# BluePillF4.net
KiCad netlist of a schematic drawn in EAGLE
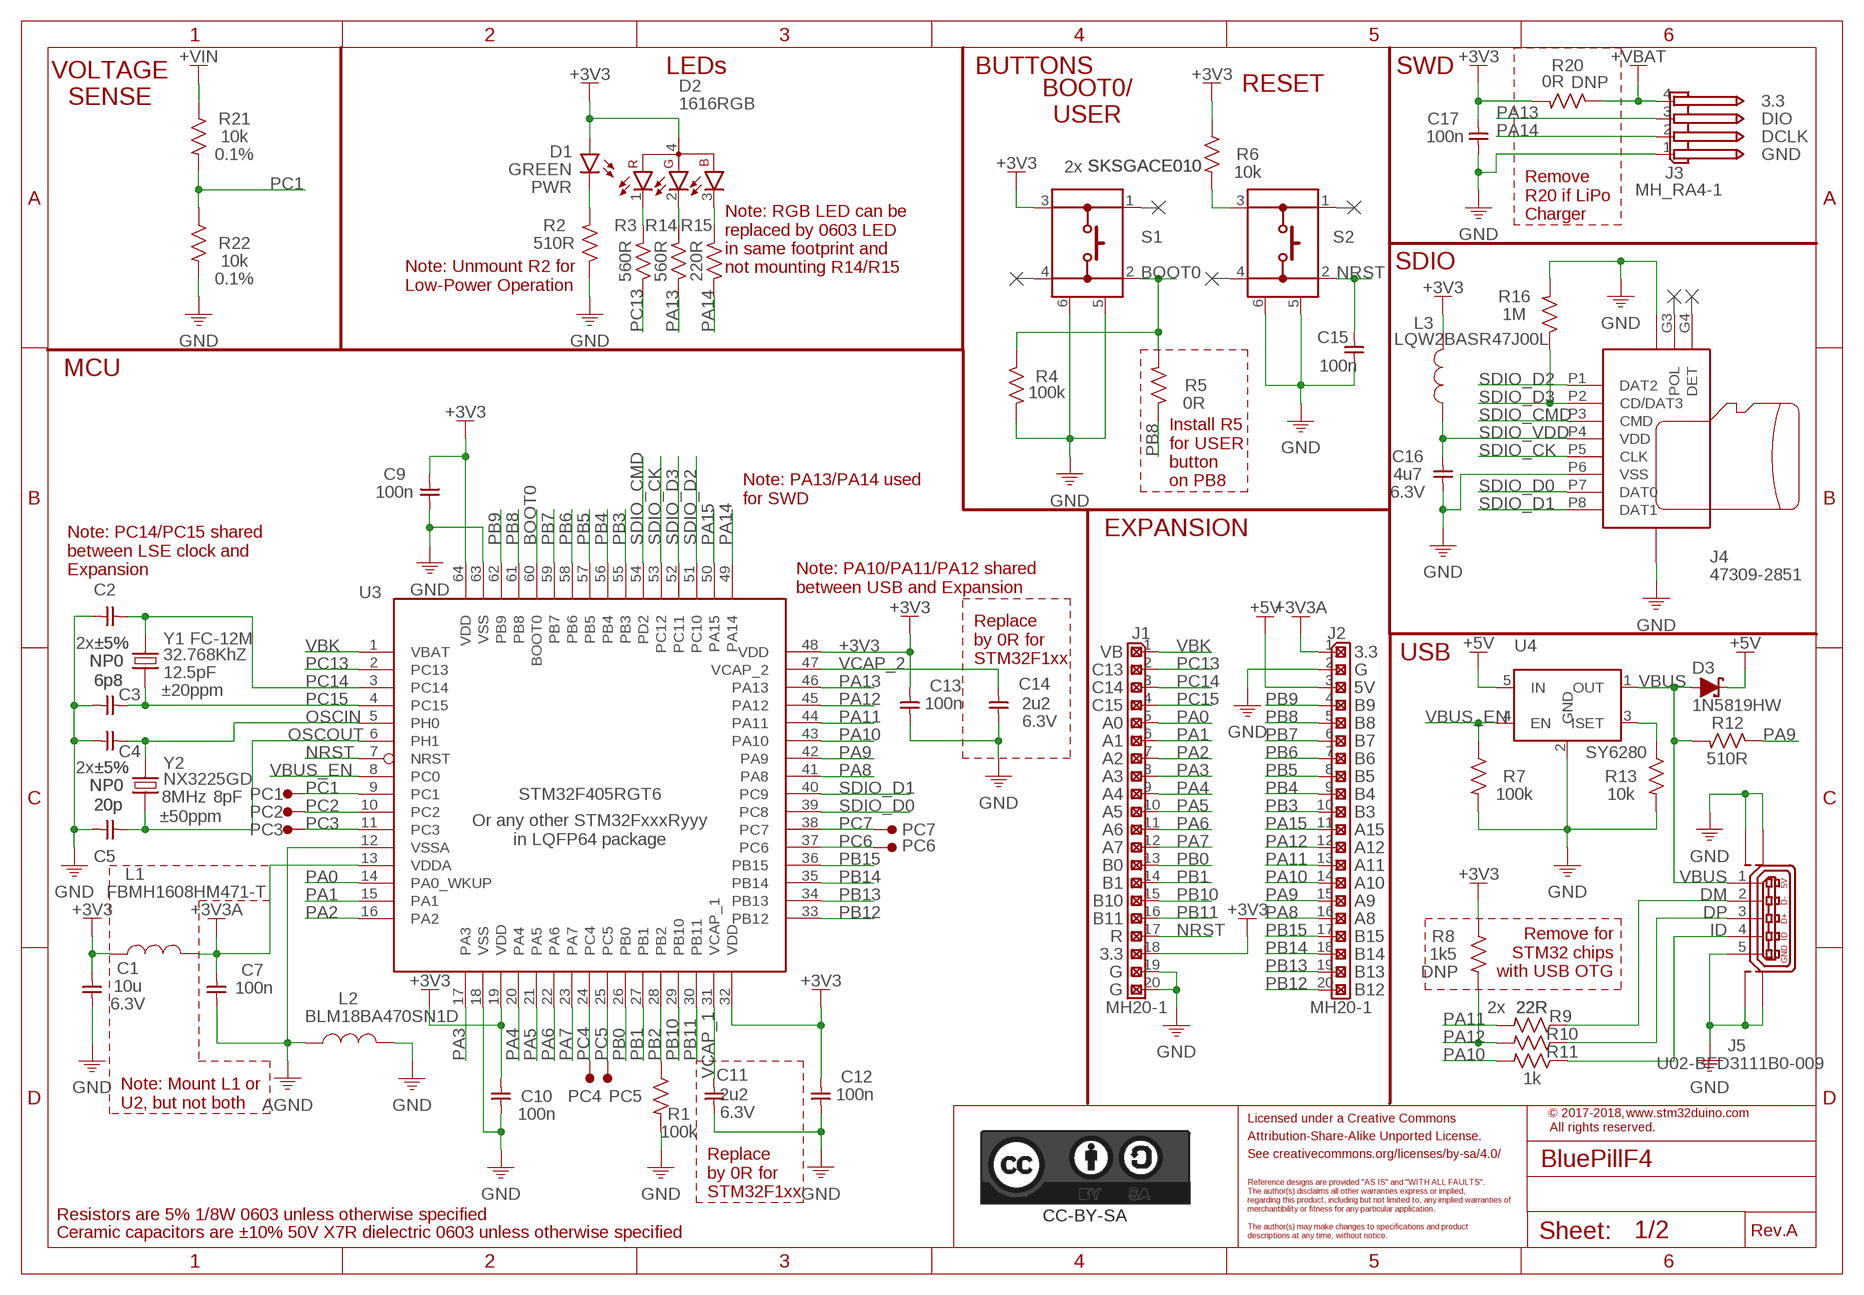
[diagram p0: schematic, sheet 1]
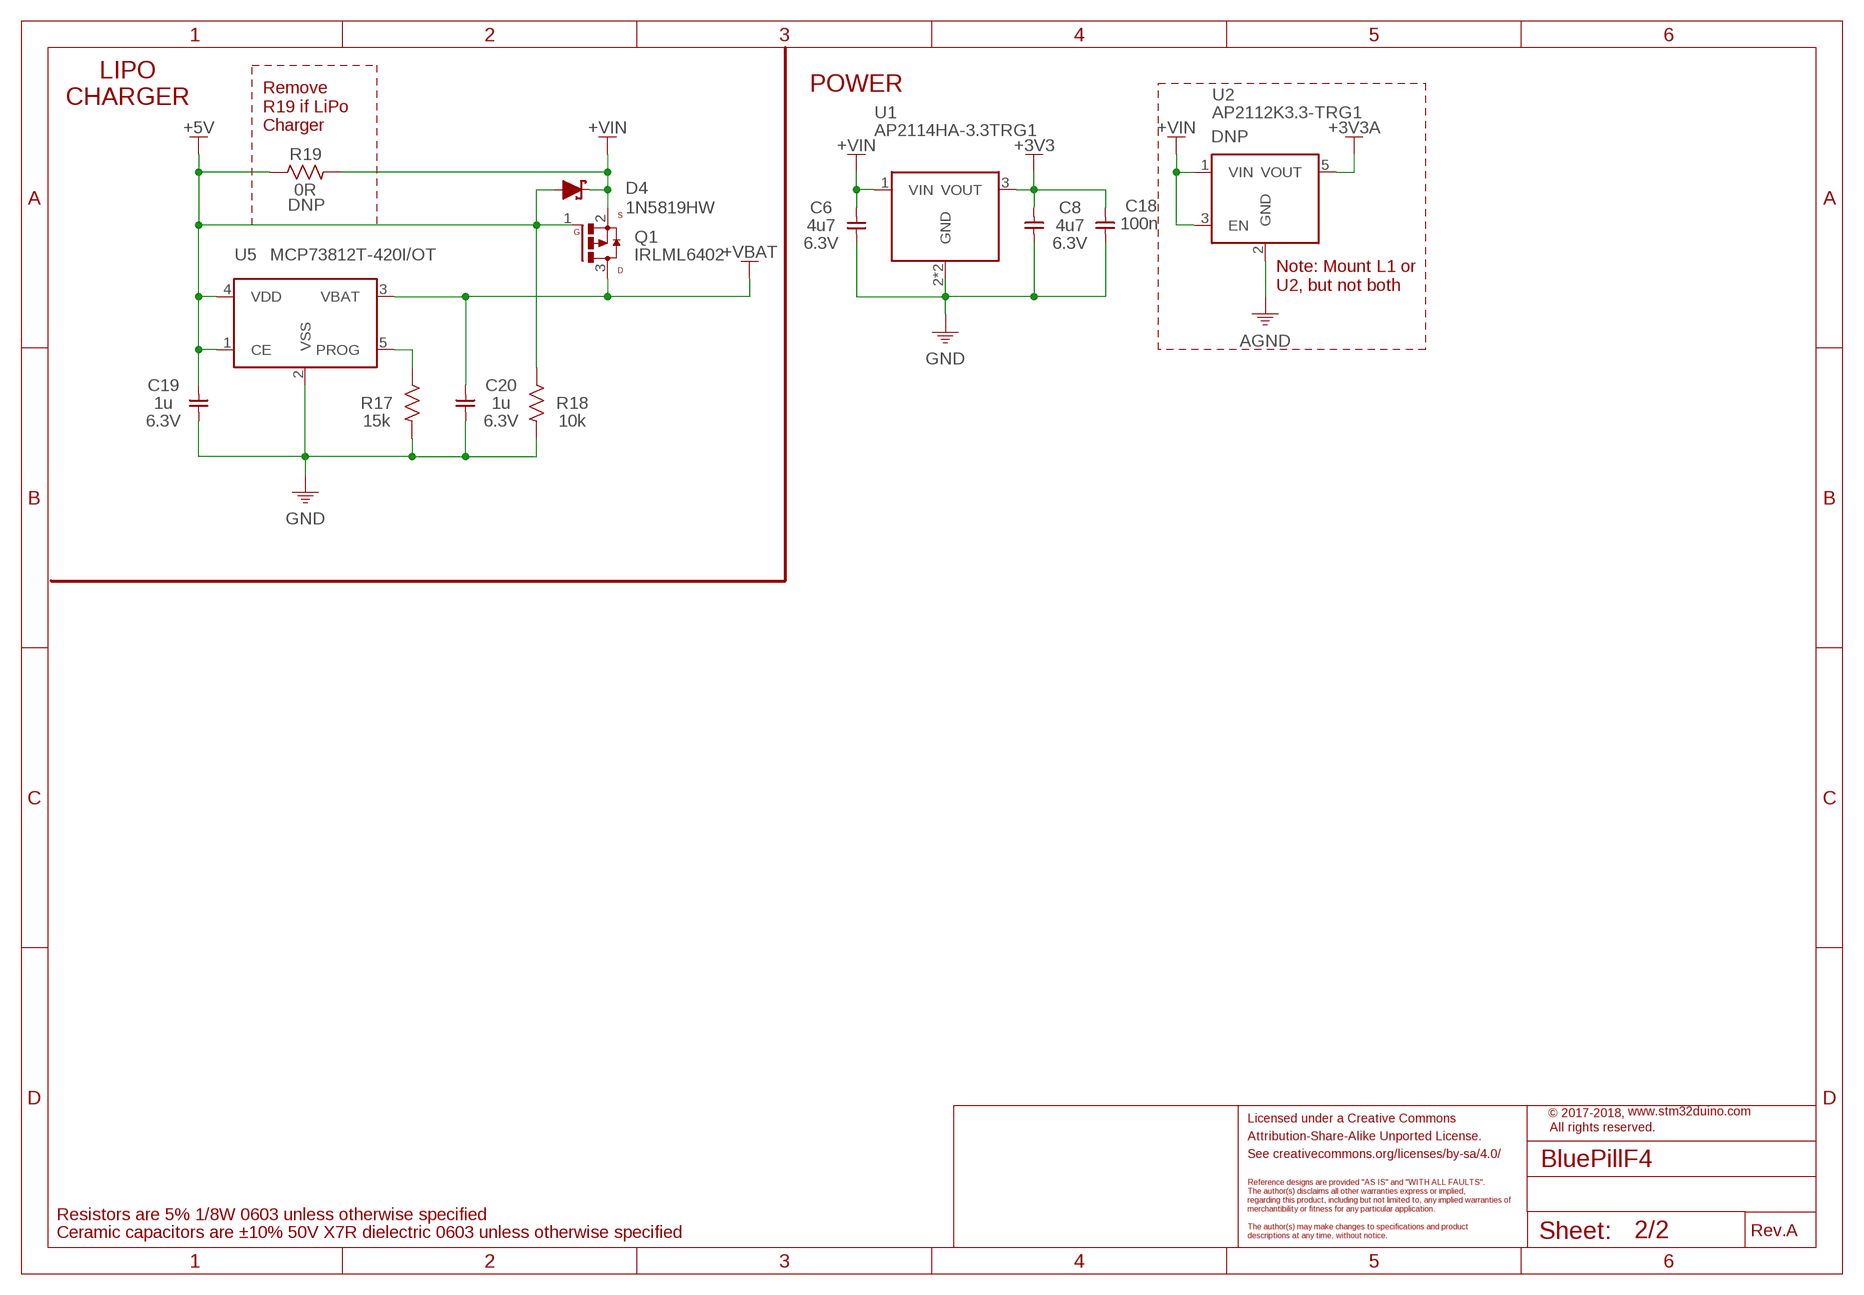
[diagram p1: schematic, sheet 2]

(export (version "E")
  (design (tool "Eeschema 10.0.6"))
  (components
    (comp (ref "C1")
      (value "10u")
      (footprint "eagle-import:C0603")
      (fields (field (name "PARTNO") "C0603_10u_X7R_10%_CER_6V3") (field (name "VOLT") "6.3V"))
      (libsource (lib "eagle-import") (part "CAP_0603"))
    )
    (comp (ref "C2")
      (value "6p8")
      (footprint "eagle-import:C0603")
      (fields
        (field (name "PARTNO") "C0603_6p8_NP0_5%_CER_50V")
        (field (name "TC") "NP0")
        (field (name "TOL") "±5%")
      )
      (libsource (lib "eagle-import") (part "CAP_0603"))
    )
    (comp (ref "C3")
      (value "6p8")
      (footprint "eagle-import:C0603")
      (fields
        (field (name "PARTNO") "C0603_6p8_NP0_5%_CER_50V")
        (field (name "TC") "NP0")
        (field (name "TOL") "±5%")
      )
      (libsource (lib "eagle-import") (part "CAP_0603"))
    )
    (comp (ref "C4")
      (value "20p")
      (footprint "eagle-import:C0603")
      (fields
        (field (name "PARTNO") "C0603_20p_NP0_5%_CER_50V")
        (field (name "TC") "NP0")
        (field (name "TOL") "±5%")
      )
      (libsource (lib "eagle-import") (part "CAP_0603"))
    )
    (comp (ref "C5")
      (value "20p")
      (footprint "eagle-import:C0603")
      (fields
        (field (name "PARTNO") "C0603_20p_NP0_5%_CER_50V")
        (field (name "TC") "NP0")
        (field (name "TOL") "±5%")
      )
      (libsource (lib "eagle-import") (part "CAP_0603"))
    )
    (comp (ref "C7")
      (value "100n")
      (footprint "eagle-import:C0603")
      (fields (field (name "PARTNO") "C0603_100n_X7R_10%_CER_50V"))
      (libsource (lib "eagle-import") (part "CAP_0603"))
    )
    (comp (ref "C9")
      (value "100n")
      (footprint "eagle-import:C0603")
      (fields (field (name "PARTNO") "C0603_100n_X7R_10%_CER_50V"))
      (libsource (lib "eagle-import") (part "CAP_0603"))
    )
    (comp (ref "C10")
      (value "100n")
      (footprint "eagle-import:C0603")
      (fields (field (name "PARTNO") "C0603_100n_X7R_10%_CER_50V"))
      (libsource (lib "eagle-import") (part "CAP_0603"))
    )
    (comp (ref "C11")
      (value "2u2")
      (footprint "eagle-import:C0603")
      (fields (field (name "PARTNO") "C0603_2u2_X7R_10%_CER_6V3") (field (name "VOLT") "6.3V"))
      (libsource (lib "eagle-import") (part "CAP_0603"))
    )
    (comp (ref "C12")
      (value "100n")
      (footprint "eagle-import:C0603")
      (fields (field (name "PARTNO") "C0603_100n_X7R_10%_CER_50V"))
      (libsource (lib "eagle-import") (part "CAP_0603"))
    )
    (comp (ref "C13")
      (value "100n")
      (footprint "eagle-import:C0603")
      (fields (field (name "PARTNO") "C0603_100n_X7R_10%_CER_50V"))
      (libsource (lib "eagle-import") (part "CAP_0603"))
    )
    (comp (ref "C14")
      (value "2u2")
      (footprint "eagle-import:C0603")
      (fields (field (name "PARTNO") "C0603_2u2_X7R_10%_CER_6V3") (field (name "VOLT") "6.3V"))
      (libsource (lib "eagle-import") (part "CAP_0603"))
    )
    (comp (ref "C15")
      (value "100n")
      (footprint "eagle-import:C0603")
      (fields (field (name "PARTNO") "C0603_100n_X7R_10%_CER_50V"))
      (libsource (lib "eagle-import") (part "CAP_0603"))
    )
    (comp (ref "C16")
      (value "4u7")
      (footprint "eagle-import:C0603")
      (fields (field (name "PARTNO") "C0603_4u7_X7R_10%_CER_6V3") (field (name "VOLT") "6.3V"))
      (libsource (lib "eagle-import") (part "CAP_0603"))
    )
    (comp (ref "C17")
      (value "100n")
      (footprint "eagle-import:C0603")
      (fields (field (name "PARTNO") "C0603_100n_X7R_10%_CER_50V"))
      (libsource (lib "eagle-import") (part "CAP_0603"))
    )
    (comp (ref "D1")
      (value "GREEN")
      (footprint "eagle-import:LED0603")
      (fields (field (name "PARTNO") "LED0603-GREEN"))
      (libsource (lib "eagle-import") (part "LED_0603"))
    )
    (comp (ref "D2")
      (value "1616RGB")
      (footprint "eagle-import:1616RGB")
      (fields (field (name "PARTNO") "LED1616-RGB"))
      (libsource (lib "eagle-import") (part "1616RGB"))
    )
    (comp (ref "D3")
      (value "1N5819HW")
      (footprint "eagle-import:SOD-123")
      (libsource (lib "eagle-import") (part "1N5819HW"))
    )
    (comp (ref "J1")
      (value "MH20-1")
      (footprint "eagle-import:MH20-1-0.1")
      (fields (field (name "PARTNO") "MH20-1-0.1"))
      (libsource (lib "eagle-import") (part "MH20-1"))
    )
    (comp (ref "J2")
      (value "MH20-1")
      (footprint "eagle-import:MH20-1-0.1")
      (fields (field (name "PARTNO") "MH20-1-0.1"))
      (libsource (lib "eagle-import") (part "MH20-1"))
    )
    (comp (ref "J3")
      (value "MH_RA4-1")
      (footprint "eagle-import:MH_RA4-1-0.1")
      (fields (field (name "PARTNO") "MH_RA4-1-0.1"))
      (libsource (lib "eagle-import") (part "MH_RA4-1"))
    )
    (comp (ref "J4")
      (value "47309-2851")
      (footprint "eagle-import:47309-2851")
      (libsource (lib "eagle-import") (part "47309-2851"))
    )
    (comp (ref "J5")
      (value "U02-BFD3111B0-009")
      (footprint "eagle-import:U02-BFD3111B0-009")
      (libsource (lib "eagle-import") (part "U02-BFD3111B0-009"))
    )
    (comp (ref "L1")
      (value "FBMH1608HM471-T")
      (footprint "eagle-import:FB0603")
      (libsource (lib "eagle-import") (part "FB_0603"))
    )
    (comp (ref "L2")
      (value "BLM18BA470SN1D")
      (footprint "eagle-import:FB0603")
      (libsource (lib "eagle-import") (part "FB_0603"))
    )
    (comp (ref "L3")
      (value "LQW2BASR47J00L")
      (footprint "eagle-import:FB0805")
      (libsource (lib "eagle-import") (part "FB_0805"))
    )
    (comp (ref "LOGO1")
      (value "CC-BY-SA_LOGO")
      (footprint "eagle-import:CC-BY-SA_LOGO")
      (libsource (lib "eagle-import") (part "CC-BY-SA_LOGO"))
    )
    (comp (ref "PC1")
      (value "TEST_PAD")
      (footprint "eagle-import:TEST_PAD")
      (libsource (lib "eagle-import") (part "TEST_PAD"))
    )
    (comp (ref "PC2")
      (value "TEST_PAD")
      (footprint "eagle-import:TEST_PAD")
      (libsource (lib "eagle-import") (part "TEST_PAD"))
    )
    (comp (ref "PC3")
      (value "TEST_PAD")
      (footprint "eagle-import:TEST_PAD")
      (libsource (lib "eagle-import") (part "TEST_PAD"))
    )
    (comp (ref "PC4")
      (value "TEST_PAD")
      (footprint "eagle-import:TEST_PAD")
      (libsource (lib "eagle-import") (part "TEST_PAD"))
    )
    (comp (ref "PC5")
      (value "TEST_PAD")
      (footprint "eagle-import:TEST_PAD")
      (libsource (lib "eagle-import") (part "TEST_PAD"))
    )
    (comp (ref "PC6")
      (value "TEST_PAD")
      (footprint "eagle-import:TEST_PAD")
      (libsource (lib "eagle-import") (part "TEST_PAD"))
    )
    (comp (ref "PC7")
      (value "TEST_PAD")
      (footprint "eagle-import:TEST_PAD")
      (libsource (lib "eagle-import") (part "TEST_PAD"))
    )
    (comp (ref "R1")
      (value "100k")
      (footprint "eagle-import:R0603")
      (fields (field (name "PARTNO") "R0603_100k_5%_125mW"))
      (libsource (lib "eagle-import") (part "RES_0603"))
    )
    (comp (ref "R2")
      (value "510R")
      (footprint "eagle-import:R0603")
      (fields (field (name "PARTNO") "R0603_510R_5%_125mW"))
      (libsource (lib "eagle-import") (part "RES_0603"))
    )
    (comp (ref "R3")
      (value "560R")
      (footprint "eagle-import:R0603")
      (fields (field (name "PARTNO") "R0603_510R_5%_125mW"))
      (libsource (lib "eagle-import") (part "RES_0603"))
    )
    (comp (ref "R4")
      (value "100k")
      (footprint "eagle-import:R0603")
      (fields (field (name "PARTNO") "R0603_100k_5%_125mW"))
      (libsource (lib "eagle-import") (part "RES_0603"))
    )
    (comp (ref "R5")
      (value "0R")
      (footprint "eagle-import:R0603")
      (fields (field (name "PARTNO") "R0603_510R_5%_125mW"))
      (libsource (lib "eagle-import") (part "RES_0603"))
    )
    (comp (ref "R6")
      (value "10k")
      (footprint "eagle-import:R0603")
      (fields (field (name "PARTNO") "R0603_10k_5%_125mW"))
      (libsource (lib "eagle-import") (part "RES_0603"))
    )
    (comp (ref "R7")
      (value "100k")
      (footprint "eagle-import:R0603")
      (fields (field (name "PARTNO") "R0603_100k_5%_125mW"))
      (libsource (lib "eagle-import") (part "RES_0603"))
    )
    (comp (ref "R8")
      (value "1k5")
      (footprint "eagle-import:R0603")
      (fields (field (name "PARTNO") "R0603_1k5_5%_125mW"))
      (libsource (lib "eagle-import") (part "RES_0603"))
    )
    (comp (ref "R9")
      (value "22R")
      (footprint "eagle-import:R0603")
      (fields (field (name "PARTNO") "R0603_22R_5%_125mW"))
      (libsource (lib "eagle-import") (part "RES_0603"))
    )
    (comp (ref "R10")
      (value "22R")
      (footprint "eagle-import:R0603")
      (fields (field (name "PARTNO") "R0603_22R_5%_125mW"))
      (libsource (lib "eagle-import") (part "RES_0603"))
    )
    (comp (ref "R11")
      (value "1k")
      (footprint "eagle-import:R0603")
      (fields (field (name "PARTNO") "R0603_1k_5%_125mW"))
      (libsource (lib "eagle-import") (part "RES_0603"))
    )
    (comp (ref "R12")
      (value "510R")
      (footprint "eagle-import:R0603")
      (fields (field (name "PARTNO") "R0603_510R_5%_125mW"))
      (libsource (lib "eagle-import") (part "RES_0603"))
    )
    (comp (ref "R13")
      (value "10k")
      (footprint "eagle-import:R0603")
      (fields (field (name "PARTNO") "R0603_10k_5%_125mW"))
      (libsource (lib "eagle-import") (part "RES_0603"))
    )
    (comp (ref "R14")
      (value "560R")
      (footprint "eagle-import:R0603")
      (fields (field (name "PARTNO") "R0603_510R_5%_125mW"))
      (libsource (lib "eagle-import") (part "RES_0603"))
    )
    (comp (ref "R15")
      (value "220R")
      (footprint "eagle-import:R0603")
      (fields (field (name "PARTNO") "R0603_510R_5%_125mW"))
      (libsource (lib "eagle-import") (part "RES_0603"))
    )
    (comp (ref "R16")
      (value "1M")
      (footprint "eagle-import:R0603")
      (fields (field (name "PARTNO") "R0603_1M_5%_125mW"))
      (libsource (lib "eagle-import") (part "RES_0603"))
    )
    (comp (ref "R20")
      (value "0R")
      (footprint "eagle-import:R0603")
      (fields (field (name "PARTNO") "R0603_510R_5%_125mW"))
      (libsource (lib "eagle-import") (part "RES_0603"))
    )
    (comp (ref "R21")
      (value "10k")
      (footprint "eagle-import:R0603")
      (fields (field (name "PARTNO") "R0603_10k_0.1%_125mW") (field (name "TOL") "0.1%"))
      (libsource (lib "eagle-import") (part "RES_0603"))
    )
    (comp (ref "R22")
      (value "10k")
      (footprint "eagle-import:R0603")
      (fields (field (name "PARTNO") "R0603_10k_0.1%_125mW") (field (name "TOL") "0.1%"))
      (libsource (lib "eagle-import") (part "RES_0603"))
    )
    (comp (ref "S1")
      (value "SKSGACE010")
      (footprint "eagle-import:SKSGACE010")
      (libsource (lib "eagle-import") (part "SKSGACE010"))
    )
    (comp (ref "S2")
      (value "SKSGACE010")
      (footprint "eagle-import:SKSGACE010")
      (libsource (lib "eagle-import") (part "SKSGACE010"))
    )
    (comp (ref "U3")
      (value "STM32F405RGT6")
      (footprint "eagle-import:LQFP64")
      (libsource (lib "eagle-import") (part "STM32F405?RGT6"))
    )
    (comp (ref "U4")
      (value "SY6280")
      (footprint "eagle-import:SOT23-5")
      (fields (field (name "PARTNO") "SY6280AAC"))
      (libsource (lib "eagle-import") (part "SY6280"))
    )
    (comp (ref "Y1")
      (value "FC-12M")
      (footprint "eagle-import:FC-12M")
      (fields
        (field (name "CAP") "12.5pF")
        (field (name "FREQ") "32.768KhZ")
        (field (name "PARTNO") "FC-12M 32.7680KA-A3")
        (field (name "TOL") "±20ppm")
      )
      (libsource (lib "eagle-import") (part "FC-12M"))
    )
    (comp (ref "Y2")
      (value "NX3225GD")
      (footprint "eagle-import:CRYSTAL_32X25_2P")
      (fields
        (field (name "CAP") "8pF")
        (field (name "FREQ") "8MHz")
        (field (name "PARTNO") "NX3225GD-8MHZ-STD-CRA-3")
        (field (name "TOL") "±50ppm")
      )
      (libsource (lib "eagle-import") (part "NX3225GD"))
    )
    (comp (ref "C6")
      (value "4u7")
      (footprint "eagle-import:C0603")
      (fields (field (name "PARTNO") "C0603_4u7_X7R_10%_CER_6V3") (field (name "VOLT") "6.3V"))
      (libsource (lib "eagle-import") (part "CAP_0603"))
    )
    (comp (ref "C8")
      (value "4u7")
      (footprint "eagle-import:C0603")
      (fields (field (name "PARTNO") "C0603_4u7_X7R_10%_CER_6V3") (field (name "VOLT") "6.3V"))
      (libsource (lib "eagle-import") (part "CAP_0603"))
    )
    (comp (ref "C18")
      (value "100n")
      (footprint "eagle-import:C0603")
      (fields (field (name "PARTNO") "C0603_100n_X7R_10%_CER_50V"))
      (libsource (lib "eagle-import") (part "CAP_0603"))
    )
    (comp (ref "C19")
      (value "1u")
      (footprint "eagle-import:C0603")
      (fields (field (name "PARTNO") "C0603_1u_X7R_10%_CER_6V3") (field (name "VOLT") "6.3V"))
      (libsource (lib "eagle-import") (part "CAP_0603"))
    )
    (comp (ref "C20")
      (value "1u")
      (footprint "eagle-import:C0603")
      (fields (field (name "PARTNO") "C0603_1u_X7R_10%_CER_6V3") (field (name "VOLT") "6.3V"))
      (libsource (lib "eagle-import") (part "CAP_0603"))
    )
    (comp (ref "D4")
      (value "1N5819HW")
      (footprint "eagle-import:SOD-123")
      (libsource (lib "eagle-import") (part "1N5819HW"))
    )
    (comp (ref "Q1")
      (value "IRLML6402")
      (footprint "eagle-import:SOT323")
      (fields (field (name "PARTNO") "IRLM6402"))
      (libsource (lib "eagle-import") (part "IRLML6402"))
    )
    (comp (ref "R17")
      (value "15k")
      (footprint "eagle-import:R0603")
      (fields (field (name "PARTNO") "R0603_15k_5%_125mW"))
      (libsource (lib "eagle-import") (part "RES_0603"))
    )
    (comp (ref "R18")
      (value "10k")
      (footprint "eagle-import:R0603")
      (fields (field (name "PARTNO") "R0603_15k_5%_125mW"))
      (libsource (lib "eagle-import") (part "RES_0603"))
    )
    (comp (ref "R19")
      (value "0R")
      (footprint "eagle-import:R0603")
      (fields (field (name "PARTNO") "R06030R_5%_125mW"))
      (libsource (lib "eagle-import") (part "RES_0603"))
    )
    (comp (ref "U1")
      (value "AP2114HA-3.3TRG1")
      (footprint "eagle-import:SOT223")
      (fields (field (name "PARTNO") "AP2114HA3.3-TRG1"))
      (libsource (lib "eagle-import") (part "AP2114?-TRG1HA3.3"))
    )
    (comp (ref "U2")
      (value "AP2112K3.3-TRG1")
      (footprint "eagle-import:SOT23-5")
      (fields (field (name "PARTNO") "AP2112?K3.3-TRG1") (field (name "PARTNO_1") "AP2112K3.3-TRG1"))
      (libsource (lib "eagle-import") (part "AP2112?-TRG1K3.3"))
    )
    (comp (ref "U5")
      (value "MCP73812T-420I/OT")
      (footprint "eagle-import:SOT23-5")
      (libsource (lib "eagle-import") (part "MCP7381T-420I/OT2"))
    )
  )
  (nets
    (net (code "1") (name "+3V3") (class "Default")
      (node (ref "C1") (pin "1") (pinfunction "1_1") (pintype "passive"))
      (node (ref "C10") (pin "2") (pinfunction "2_2") (pintype "passive"))
      (node (ref "C12") (pin "1") (pinfunction "1_1") (pintype "passive"))
      (node (ref "C13") (pin "1") (pinfunction "1_1") (pintype "passive"))
      (node (ref "C17") (pin "2") (pinfunction "2_2") (pintype "passive"))
      (node (ref "C18") (pin "1") (pinfunction "1_1") (pintype "passive"))
      (node (ref "C8") (pin "1") (pinfunction "1_1") (pintype "passive"))
      (node (ref "C9") (pin "2") (pinfunction "2_2") (pintype "passive"))
      (node (ref "D1") (pin "2") (pinfunction "A_2") (pintype "passive"))
      (node (ref "D2") (pin "4") (pinfunction "A_4") (pintype "passive"))
      (node (ref "J1") (pin "18") (pinfunction "18_18") (pintype "passive"))
      (node (ref "L1") (pin "1") (pinfunction "1_1") (pintype "passive"))
      (node (ref "L3") (pin "2") (pinfunction "2_2") (pintype "passive"))
      (node (ref "R20") (pin "2") (pinfunction "2_2") (pintype "passive"))
      (node (ref "R6") (pin "1") (pinfunction "1_1") (pintype "passive"))
      (node (ref "R8") (pin "1") (pinfunction "1_1") (pintype "passive"))
      (node (ref "S1") (pin "3") (pinfunction "A_3") (pintype "passive"))
      (node (ref "U1") (pin "3") (pinfunction "VOUT_3") (pintype "power_in"))
      (node (ref "U3") (pin "19") (pinfunction "VDD_19") (pintype "power_in"))
      (node (ref "U3") (pin "32") (pinfunction "VDD_32") (pintype "power_in"))
      (node (ref "U3") (pin "48") (pinfunction "VDD_48") (pintype "power_in"))
      (node (ref "U3") (pin "64") (pinfunction "VDD_64") (pintype "power_in"))
    )
    (net (code "2") (name "+3V3A") (class "Default")
      (node (ref "C7") (pin "2") (pinfunction "2_2") (pintype "passive"))
      (node (ref "J2") (pin "1") (pinfunction "1_1") (pintype "passive"))
      (node (ref "L1") (pin "2") (pinfunction "2_2") (pintype "passive"))
      (node (ref "U2") (pin "5") (pinfunction "VOUT_5") (pintype "power_in"))
      (node (ref "U3") (pin "13") (pinfunction "VDDA_13") (pintype "power_in"))
    )
    (net (code "3") (name "+5V") (class "Default")
      (node (ref "C19") (pin "1") (pinfunction "1_1") (pintype "passive"))
      (node (ref "D3") (pin "C") (pinfunction "C_C") (pintype "passive"))
      (node (ref "D4") (pin "A") (pinfunction "A_A") (pintype "passive"))
      (node (ref "J2") (pin "3") (pinfunction "3_3") (pintype "passive"))
      (node (ref "Q1") (pin "1") (pinfunction "G_1") (pintype "passive"))
      (node (ref "R18") (pin "1") (pinfunction "1_1") (pintype "passive"))
      (node (ref "R19") (pin "1") (pinfunction "1_1") (pintype "passive"))
      (node (ref "U4") (pin "5") (pinfunction "IN_5") (pintype "power_in"))
      (node (ref "U5") (pin "1") (pinfunction "CE_1") (pintype "input"))
      (node (ref "U5") (pin "4") (pinfunction "VDD_4") (pintype "power_in"))
    )
    (net (code "4") (name "+VBAT") (class "Default")
      (node (ref "C20") (pin "1") (pinfunction "1_1") (pintype "passive"))
      (node (ref "J3") (pin "4") (pinfunction "4_4") (pintype "passive"))
      (node (ref "Q1") (pin "3") (pinfunction "D_3") (pintype "passive"))
      (node (ref "R20") (pin "1") (pinfunction "1_1") (pintype "passive"))
      (node (ref "U5") (pin "3") (pinfunction "VBAT_3") (pintype "power_in"))
    )
    (net (code "5") (name "+VIN") (class "Default")
      (node (ref "C6") (pin "1") (pinfunction "1_1") (pintype "passive"))
      (node (ref "D4") (pin "C") (pinfunction "C_C") (pintype "passive"))
      (node (ref "Q1") (pin "2") (pinfunction "S_2") (pintype "passive"))
      (node (ref "R19") (pin "2") (pinfunction "2_2") (pintype "passive"))
      (node (ref "R21") (pin "1") (pinfunction "1_1") (pintype "passive"))
      (node (ref "U1") (pin "1") (pinfunction "VIN_1") (pintype "power_in"))
      (node (ref "U2") (pin "1") (pinfunction "VIN_1") (pintype "power_in"))
      (node (ref "U2") (pin "3") (pinfunction "EN_3") (pintype "input"))
    )
    (net (code "6") (name "AGND") (class "Default")
      (node (ref "C7") (pin "1") (pinfunction "1_1") (pintype "passive"))
      (node (ref "L2") (pin "1") (pinfunction "1_1") (pintype "passive"))
      (node (ref "U2") (pin "2") (pinfunction "GND_2") (pintype "power_in"))
      (node (ref "U3") (pin "12") (pinfunction "VSSA_12") (pintype "power_in"))
    )
    (net (code "7") (name "BOOT0") (class "Default")
      (node (ref "R4") (pin "1") (pinfunction "1_1") (pintype "passive"))
      (node (ref "R5") (pin "2") (pinfunction "2_2") (pintype "passive"))
      (node (ref "S1") (pin "2") (pinfunction "B_2") (pintype "passive"))
      (node (ref "U3") (pin "60") (pinfunction "BOOT0_60") (pintype "bidirectional"))
    )
    (net (code "8") (name "DM") (class "Default")
      (node (ref "J5") (pin "2") (pinfunction "2_2") (pintype "passive"))
      (node (ref "R9") (pin "1") (pinfunction "1_1") (pintype "passive"))
    )
    (net (code "9") (name "DP") (class "Default")
      (node (ref "J5") (pin "3") (pinfunction "3_3") (pintype "passive"))
      (node (ref "R10") (pin "1") (pinfunction "1_1") (pintype "passive"))
    )
    (net (code "10") (name "GND") (class "Default")
      (node (ref "C1") (pin "2") (pinfunction "2_2") (pintype "passive"))
      (node (ref "C10") (pin "1") (pinfunction "1_1") (pintype "passive"))
      (node (ref "C11") (pin "1") (pinfunction "1_1") (pintype "passive"))
      (node (ref "C12") (pin "2") (pinfunction "2_2") (pintype "passive"))
      (node (ref "C13") (pin "2") (pinfunction "2_2") (pintype "passive"))
      (node (ref "C14") (pin "1") (pinfunction "1_1") (pintype "passive"))
      (node (ref "C15") (pin "1") (pinfunction "1_1") (pintype "passive"))
      (node (ref "C16") (pin "1") (pinfunction "1_1") (pintype "passive"))
      (node (ref "C17") (pin "1") (pinfunction "1_1") (pintype "passive"))
      (node (ref "C18") (pin "2") (pinfunction "2_2") (pintype "passive"))
      (node (ref "C19") (pin "2") (pinfunction "2_2") (pintype "passive"))
      (node (ref "C2") (pin "2") (pinfunction "2_2") (pintype "passive"))
      (node (ref "C20") (pin "2") (pinfunction "2_2") (pintype "passive"))
      (node (ref "C3") (pin "2") (pinfunction "2_2") (pintype "passive"))
      (node (ref "C4") (pin "2") (pinfunction "2_2") (pintype "passive"))
      (node (ref "C5") (pin "2") (pinfunction "2_2") (pintype "passive"))
      (node (ref "C6") (pin "2") (pinfunction "2_2") (pintype "passive"))
      (node (ref "C8") (pin "2") (pinfunction "2_2") (pintype "passive"))
      (node (ref "C9") (pin "1") (pinfunction "1_1") (pintype "passive"))
      (node (ref "J1") (pin "19") (pinfunction "19_19") (pintype "passive"))
      (node (ref "J1") (pin "20") (pinfunction "20_20") (pintype "passive"))
      (node (ref "J2") (pin "2") (pinfunction "2_2") (pintype "passive"))
      (node (ref "J3") (pin "1") (pinfunction "1_1") (pintype "passive"))
      (node (ref "J4") (pin "G1") (pinfunction "GND_G1") (pintype "power_in"))
      (node (ref "J4") (pin "G2") (pinfunction "GND_G2") (pintype "power_in"))
      (node (ref "J4") (pin "P6") (pinfunction "VSS_P6") (pintype "power_in"))
      (node (ref "J5") (pin "5") (pinfunction "5_5") (pintype "passive"))
      (node (ref "J5") (pin "S$1") (pinfunction "M0_S$1") (pintype "passive"))
      (node (ref "J5") (pin "S$2") (pinfunction "M1_S$2") (pintype "passive"))
      (node (ref "J5") (pin "S$3") (pinfunction "M2_S$3") (pintype "passive"))
      (node (ref "J5") (pin "S$4") (pinfunction "M3_S$4") (pintype "passive"))
      (node (ref "L2") (pin "2") (pinfunction "2_2") (pintype "passive"))
      (node (ref "R1") (pin "2") (pinfunction "2_2") (pintype "passive"))
      (node (ref "R13") (pin "2") (pinfunction "2_2") (pintype "passive"))
      (node (ref "R16") (pin "2") (pinfunction "2_2") (pintype "passive"))
      (node (ref "R17") (pin "2") (pinfunction "2_2") (pintype "passive"))
      (node (ref "R18") (pin "2") (pinfunction "2_2") (pintype "passive"))
      (node (ref "R2") (pin "1") (pinfunction "1_1") (pintype "passive"))
      (node (ref "R22") (pin "2") (pinfunction "2_2") (pintype "passive"))
      (node (ref "R4") (pin "2") (pinfunction "2_2") (pintype "passive"))
      (node (ref "R7") (pin "2") (pinfunction "2_2") (pintype "passive"))
      (node (ref "S1") (pin "5") (pinfunction "5_5") (pintype "passive"))
      (node (ref "S1") (pin "6") (pinfunction "6_6") (pintype "passive"))
      (node (ref "S2") (pin "5") (pinfunction "5_5") (pintype "passive"))
      (node (ref "S2") (pin "6") (pinfunction "6_6") (pintype "passive"))
      (node (ref "U1") (pin "2") (pinfunction "GND_2") (pintype "power_in"))
      (node (ref "U1") (pin "PAD") (pinfunction "GND_PAD") (pintype "power_in"))
      (node (ref "U3") (pin "18") (pinfunction "VSS_18") (pintype "power_in"))
      (node (ref "U3") (pin "63") (pinfunction "VSS_63") (pintype "power_in"))
      (node (ref "U4") (pin "2") (pinfunction "GND_2") (pintype "power_in"))
      (node (ref "U5") (pin "2") (pinfunction "VSS_2") (pintype "power_in"))
    )
    (net (code "11") (name "ID") (class "Default")
      (node (ref "J5") (pin "4") (pinfunction "4_4") (pintype "passive"))
      (node (ref "R11") (pin "1") (pinfunction "1_1") (pintype "passive"))
    )
    (net (code "12") (name "NRST") (class "Default")
      (node (ref "C15") (pin "2") (pinfunction "2_2") (pintype "passive"))
      (node (ref "J1") (pin "17") (pinfunction "17_17") (pintype "passive"))
      (node (ref "S2") (pin "2") (pinfunction "B_2") (pintype "passive"))
      (node (ref "U3") (pin "7") (pinfunction "NRST_7") (pintype "input"))
    )
    (net (code "13") (name "Net-(D1-C)") (class "Default")
      (node (ref "D1") (pin "1") (pinfunction "C_1") (pintype "passive"))
      (node (ref "R2") (pin "2") (pinfunction "2_2") (pintype "passive"))
    )
    (net (code "14") (name "Net-(D2-CB)") (class "Default")
      (node (ref "D2") (pin "3") (pinfunction "CB_3") (pintype "passive"))
      (node (ref "R15") (pin "2") (pinfunction "2_2") (pintype "passive"))
    )
    (net (code "15") (name "Net-(D2-CG)") (class "Default")
      (node (ref "D2") (pin "2") (pinfunction "CG_2") (pintype "passive"))
      (node (ref "R14") (pin "2") (pinfunction "2_2") (pintype "passive"))
    )
    (net (code "16") (name "Net-(D2-CR)") (class "Default")
      (node (ref "D2") (pin "1") (pinfunction "CR_1") (pintype "passive"))
      (node (ref "R3") (pin "2") (pinfunction "2_2") (pintype "passive"))
    )
    (net (code "17") (name "Net-(R6-Pad2)") (class "Default")
      (node (ref "R6") (pin "2") (pinfunction "2_2") (pintype "passive"))
      (node (ref "S2") (pin "3") (pinfunction "A_3") (pintype "passive"))
    )
    (net (code "18") (name "Net-(U4-ISET)") (class "Default")
      (node (ref "R13") (pin "1") (pinfunction "1_1") (pintype "passive"))
      (node (ref "U4") (pin "3") (pinfunction "ISET_3") (pintype "passive"))
    )
    (net (code "19") (name "Net-(U5-PROG)") (class "Default")
      (node (ref "R17") (pin "1") (pinfunction "1_1") (pintype "passive"))
      (node (ref "U5") (pin "5") (pinfunction "PROG_5") (pintype "passive"))
    )
    (net (code "20") (name "OSCIN") (class "Default")
      (node (ref "C4") (pin "1") (pinfunction "1_1") (pintype "passive"))
      (node (ref "U3") (pin "5") (pinfunction "PH0_5") (pintype "bidirectional"))
      (node (ref "Y2") (pin "2") (pinfunction "2_2") (pintype "passive"))
    )
    (net (code "21") (name "OSCOUT") (class "Default")
      (node (ref "C5") (pin "1") (pinfunction "1_1") (pintype "passive"))
      (node (ref "U3") (pin "6") (pinfunction "PH1_6") (pintype "bidirectional"))
      (node (ref "Y2") (pin "1") (pinfunction "1_1") (pintype "passive"))
    )
    (net (code "22") (name "PA0") (class "Default")
      (node (ref "J1") (pin "5") (pinfunction "5_5") (pintype "passive"))
      (node (ref "U3") (pin "14") (pinfunction "PA0_WKUP_14") (pintype "bidirectional"))
    )
    (net (code "23") (name "PA1") (class "Default")
      (node (ref "J1") (pin "6") (pinfunction "6_6") (pintype "passive"))
      (node (ref "U3") (pin "15") (pinfunction "PA1_15") (pintype "bidirectional"))
    )
    (net (code "24") (name "PA2") (class "Default")
      (node (ref "J1") (pin "7") (pinfunction "7_7") (pintype "passive"))
      (node (ref "U3") (pin "16") (pinfunction "PA2_16") (pintype "bidirectional"))
    )
    (net (code "25") (name "PA3") (class "Default")
      (node (ref "J1") (pin "8") (pinfunction "8_8") (pintype "passive"))
      (node (ref "U3") (pin "17") (pinfunction "PA3_17") (pintype "bidirectional"))
    )
    (net (code "26") (name "PA4") (class "Default")
      (node (ref "J1") (pin "9") (pinfunction "9_9") (pintype "passive"))
      (node (ref "U3") (pin "20") (pinfunction "PA4_20") (pintype "bidirectional"))
    )
    (net (code "27") (name "PA5") (class "Default")
      (node (ref "J1") (pin "10") (pinfunction "10_10") (pintype "passive"))
      (node (ref "U3") (pin "21") (pinfunction "PA5_21") (pintype "bidirectional"))
    )
    (net (code "28") (name "PA6") (class "Default")
      (node (ref "J1") (pin "11") (pinfunction "11_11") (pintype "passive"))
      (node (ref "U3") (pin "22") (pinfunction "PA6_22") (pintype "bidirectional"))
    )
    (net (code "29") (name "PA7") (class "Default")
      (node (ref "J1") (pin "12") (pinfunction "12_12") (pintype "passive"))
      (node (ref "U3") (pin "23") (pinfunction "PA7_23") (pintype "bidirectional"))
    )
    (net (code "30") (name "PA8") (class "Default")
      (node (ref "J2") (pin "16") (pinfunction "16_16") (pintype "passive"))
      (node (ref "U3") (pin "41") (pinfunction "PA8_41") (pintype "bidirectional"))
    )
    (net (code "31") (name "PA9") (class "Default")
      (node (ref "J2") (pin "15") (pinfunction "15_15") (pintype "passive"))
      (node (ref "R12") (pin "1") (pinfunction "1_1") (pintype "passive"))
      (node (ref "U3") (pin "42") (pinfunction "PA9_42") (pintype "bidirectional"))
    )
    (net (code "32") (name "PA10") (class "Default")
      (node (ref "J2") (pin "14") (pinfunction "14_14") (pintype "passive"))
      (node (ref "R11") (pin "2") (pinfunction "2_2") (pintype "passive"))
      (node (ref "U3") (pin "43") (pinfunction "PA10_43") (pintype "bidirectional"))
    )
    (net (code "33") (name "PA11") (class "Default")
      (node (ref "J2") (pin "13") (pinfunction "13_13") (pintype "passive"))
      (node (ref "R9") (pin "2") (pinfunction "2_2") (pintype "passive"))
      (node (ref "U3") (pin "44") (pinfunction "PA11_44") (pintype "bidirectional"))
    )
    (net (code "34") (name "PA12") (class "Default")
      (node (ref "J2") (pin "12") (pinfunction "12_12") (pintype "passive"))
      (node (ref "R10") (pin "2") (pinfunction "2_2") (pintype "passive"))
      (node (ref "R8") (pin "2") (pinfunction "2_2") (pintype "passive"))
      (node (ref "U3") (pin "45") (pinfunction "PA12_45") (pintype "bidirectional"))
    )
    (net (code "35") (name "PA13") (class "Default")
      (node (ref "J3") (pin "3") (pinfunction "3_3") (pintype "passive"))
      (node (ref "R14") (pin "1") (pinfunction "1_1") (pintype "passive"))
      (node (ref "U3") (pin "46") (pinfunction "PA13_46") (pintype "bidirectional"))
    )
    (net (code "36") (name "PA14") (class "Default")
      (node (ref "J3") (pin "2") (pinfunction "2_2") (pintype "passive"))
      (node (ref "R15") (pin "1") (pinfunction "1_1") (pintype "passive"))
      (node (ref "U3") (pin "49") (pinfunction "PA14_49") (pintype "bidirectional"))
    )
    (net (code "37") (name "PA15") (class "Default")
      (node (ref "J2") (pin "11") (pinfunction "11_11") (pintype "passive"))
      (node (ref "U3") (pin "50") (pinfunction "PA15_50") (pintype "bidirectional"))
    )
    (net (code "38") (name "PB0") (class "Default")
      (node (ref "J1") (pin "13") (pinfunction "13_13") (pintype "passive"))
      (node (ref "U3") (pin "26") (pinfunction "PB0_26") (pintype "bidirectional"))
    )
    (net (code "39") (name "PB1") (class "Default")
      (node (ref "J1") (pin "14") (pinfunction "14_14") (pintype "passive"))
      (node (ref "U3") (pin "27") (pinfunction "PB1_27") (pintype "bidirectional"))
    )
    (net (code "40") (name "PB2") (class "Default")
      (node (ref "R1") (pin "1") (pinfunction "1_1") (pintype "passive"))
      (node (ref "U3") (pin "28") (pinfunction "PB2_28") (pintype "bidirectional"))
    )
    (net (code "41") (name "PB3") (class "Default")
      (node (ref "J2") (pin "10") (pinfunction "10_10") (pintype "passive"))
      (node (ref "U3") (pin "55") (pinfunction "PB3_55") (pintype "bidirectional"))
    )
    (net (code "42") (name "PB4") (class "Default")
      (node (ref "J2") (pin "9") (pinfunction "9_9") (pintype "passive"))
      (node (ref "U3") (pin "56") (pinfunction "PB4_56") (pintype "bidirectional"))
    )
    (net (code "43") (name "PB5") (class "Default")
      (node (ref "J2") (pin "8") (pinfunction "8_8") (pintype "passive"))
      (node (ref "U3") (pin "57") (pinfunction "PB5_57") (pintype "bidirectional"))
    )
    (net (code "44") (name "PB6") (class "Default")
      (node (ref "J2") (pin "7") (pinfunction "7_7") (pintype "passive"))
      (node (ref "U3") (pin "58") (pinfunction "PB6_58") (pintype "bidirectional"))
    )
    (net (code "45") (name "PB7") (class "Default")
      (node (ref "J2") (pin "6") (pinfunction "6_6") (pintype "passive"))
      (node (ref "U3") (pin "59") (pinfunction "PB7_59") (pintype "bidirectional"))
    )
    (net (code "46") (name "PB8") (class "Default")
      (node (ref "J2") (pin "5") (pinfunction "5_5") (pintype "passive"))
      (node (ref "R5") (pin "1") (pinfunction "1_1") (pintype "passive"))
      (node (ref "U3") (pin "61") (pinfunction "PB8_61") (pintype "bidirectional"))
    )
    (net (code "47") (name "PB9") (class "Default")
      (node (ref "J2") (pin "4") (pinfunction "4_4") (pintype "passive"))
      (node (ref "U3") (pin "62") (pinfunction "PB9_62") (pintype "bidirectional"))
    )
    (net (code "48") (name "PB10") (class "Default")
      (node (ref "J1") (pin "15") (pinfunction "15_15") (pintype "passive"))
      (node (ref "U3") (pin "29") (pinfunction "PB10_29") (pintype "bidirectional"))
    )
    (net (code "49") (name "PB11") (class "Default")
      (node (ref "J1") (pin "16") (pinfunction "16_16") (pintype "passive"))
      (node (ref "U3") (pin "30") (pinfunction "PB11_30") (pintype "bidirectional"))
    )
    (net (code "50") (name "PB12") (class "Default")
      (node (ref "J2") (pin "20") (pinfunction "20_20") (pintype "passive"))
      (node (ref "U3") (pin "33") (pinfunction "PB12_33") (pintype "bidirectional"))
    )
    (net (code "51") (name "PB13") (class "Default")
      (node (ref "J2") (pin "19") (pinfunction "19_19") (pintype "passive"))
      (node (ref "U3") (pin "34") (pinfunction "PB13_34") (pintype "bidirectional"))
    )
    (net (code "52") (name "PB14") (class "Default")
      (node (ref "J2") (pin "18") (pinfunction "18_18") (pintype "passive"))
      (node (ref "U3") (pin "35") (pinfunction "PB14_35") (pintype "bidirectional"))
    )
    (net (code "53") (name "PB15") (class "Default")
      (node (ref "J2") (pin "17") (pinfunction "17_17") (pintype "passive"))
      (node (ref "U3") (pin "36") (pinfunction "PB15_36") (pintype "bidirectional"))
    )
    (net (code "54") (name "PC1") (class "Default")
      (node (ref "PC1") (pin "1") (pinfunction "PP_1") (pintype "passive"))
      (node (ref "R21") (pin "2") (pinfunction "2_2") (pintype "passive"))
      (node (ref "R22") (pin "1") (pinfunction "1_1") (pintype "passive"))
      (node (ref "U3") (pin "9") (pinfunction "PC1_9") (pintype "bidirectional"))
    )
    (net (code "55") (name "PC2") (class "Default")
      (node (ref "PC2") (pin "1") (pinfunction "PP_1") (pintype "passive"))
      (node (ref "U3") (pin "10") (pinfunction "PC2_10") (pintype "bidirectional"))
    )
    (net (code "56") (name "PC3") (class "Default")
      (node (ref "PC3") (pin "1") (pinfunction "PP_1") (pintype "passive"))
      (node (ref "U3") (pin "11") (pinfunction "PC3_11") (pintype "bidirectional"))
    )
    (net (code "57") (name "PC4") (class "Default")
      (node (ref "PC4") (pin "1") (pinfunction "PP_1") (pintype "passive"))
      (node (ref "U3") (pin "24") (pinfunction "PC4_24") (pintype "bidirectional"))
    )
    (net (code "58") (name "PC5") (class "Default")
      (node (ref "PC5") (pin "1") (pinfunction "PP_1") (pintype "passive"))
      (node (ref "U3") (pin "25") (pinfunction "PC5_25") (pintype "bidirectional"))
    )
    (net (code "59") (name "PC6") (class "Default")
      (node (ref "PC6") (pin "1") (pinfunction "PP_1") (pintype "passive"))
      (node (ref "U3") (pin "37") (pinfunction "PC6_37") (pintype "bidirectional"))
    )
    (net (code "60") (name "PC7") (class "Default")
      (node (ref "PC7") (pin "1") (pinfunction "PP_1") (pintype "passive"))
      (node (ref "U3") (pin "38") (pinfunction "PC7_38") (pintype "bidirectional"))
    )
    (net (code "61") (name "PC13") (class "Default")
      (node (ref "J1") (pin "2") (pinfunction "2_2") (pintype "passive"))
      (node (ref "R3") (pin "1") (pinfunction "1_1") (pintype "passive"))
      (node (ref "U3") (pin "2") (pinfunction "PC13_2") (pintype "bidirectional"))
    )
    (net (code "62") (name "PC14") (class "Default")
      (node (ref "C2") (pin "1") (pinfunction "1_1") (pintype "passive"))
      (node (ref "J1") (pin "3") (pinfunction "3_3") (pintype "passive"))
      (node (ref "U3") (pin "3") (pinfunction "PC14_3") (pintype "bidirectional"))
      (node (ref "Y1") (pin "2") (pinfunction "2_2") (pintype "passive"))
    )
    (net (code "63") (name "PC15") (class "Default")
      (node (ref "C3") (pin "1") (pinfunction "1_1") (pintype "passive"))
      (node (ref "J1") (pin "4") (pinfunction "4_4") (pintype "passive"))
      (node (ref "U3") (pin "4") (pinfunction "PC15_4") (pintype "bidirectional"))
      (node (ref "Y1") (pin "1") (pinfunction "1_1") (pintype "passive"))
    )
    (net (code "64") (name "SDIO_CK") (class "Default")
      (node (ref "J4") (pin "P5") (pinfunction "CLK_P5") (pintype "input"))
      (node (ref "U3") (pin "53") (pinfunction "PC12_53") (pintype "bidirectional"))
    )
    (net (code "65") (name "SDIO_CMD") (class "Default")
      (node (ref "J4") (pin "P3") (pinfunction "CMD_P3") (pintype "input"))
      (node (ref "U3") (pin "54") (pinfunction "PD2_54") (pintype "bidirectional"))
    )
    (net (code "66") (name "SDIO_D0") (class "Default")
      (node (ref "J4") (pin "P7") (pinfunction "DAT0_P7") (pintype "bidirectional"))
      (node (ref "U3") (pin "39") (pinfunction "PC8_39") (pintype "bidirectional"))
    )
    (net (code "67") (name "SDIO_D1") (class "Default")
      (node (ref "J4") (pin "P8") (pinfunction "DAT1_P8") (pintype "bidirectional"))
      (node (ref "U3") (pin "40") (pinfunction "PC9_40") (pintype "bidirectional"))
    )
    (net (code "68") (name "SDIO_D2") (class "Default")
      (node (ref "J4") (pin "P1") (pinfunction "DAT2_P1") (pintype "bidirectional"))
      (node (ref "U3") (pin "51") (pinfunction "PC10_51") (pintype "bidirectional"))
    )
    (net (code "69") (name "SDIO_D3") (class "Default")
      (node (ref "J4") (pin "P2") (pinfunction "CD/DAT3_P2") (pintype "bidirectional"))
      (node (ref "R16") (pin "1") (pinfunction "1_1") (pintype "passive"))
      (node (ref "U3") (pin "52") (pinfunction "PC11_52") (pintype "bidirectional"))
    )
    (net (code "70") (name "SDIO_VDD") (class "Default")
      (node (ref "C16") (pin "2") (pinfunction "2_2") (pintype "passive"))
      (node (ref "J4") (pin "P4") (pinfunction "VDD_P4") (pintype "power_in"))
      (node (ref "L3") (pin "1") (pinfunction "1_1") (pintype "passive"))
    )
    (net (code "71") (name "VBK") (class "Default")
      (node (ref "J1") (pin "1") (pinfunction "1_1") (pintype "passive"))
      (node (ref "U3") (pin "1") (pinfunction "VBAT_1") (pintype "power_in"))
    )
    (net (code "72") (name "VBUS") (class "Default")
      (node (ref "D3") (pin "A") (pinfunction "A_A") (pintype "passive"))
      (node (ref "J5") (pin "1") (pinfunction "1_1") (pintype "passive"))
      (node (ref "R12") (pin "2") (pinfunction "2_2") (pintype "passive"))
      (node (ref "U4") (pin "1") (pinfunction "OUT_1") (pintype "power_in"))
    )
    (net (code "73") (name "VBUS_EN") (class "Default")
      (node (ref "R7") (pin "1") (pinfunction "1_1") (pintype "passive"))
      (node (ref "U3") (pin "8") (pinfunction "PC0_8") (pintype "bidirectional"))
      (node (ref "U4") (pin "4") (pinfunction "EN_4") (pintype "input"))
    )
    (net (code "74") (name "VCAP_1") (class "Default")
      (node (ref "C11") (pin "2") (pinfunction "2_2") (pintype "passive"))
      (node (ref "U3") (pin "31") (pinfunction "VCAP_1_31") (pintype "passive"))
    )
    (net (code "75") (name "VCAP_2") (class "Default")
      (node (ref "C14") (pin "2") (pinfunction "2_2") (pintype "passive"))
      (node (ref "U3") (pin "47") (pinfunction "VCAP_2_47") (pintype "passive"))
    )
    (net (code "76") (name "unconnected-(J4-DET-PadG4)") (class "Default")
      (node (ref "J4") (pin "G4") (pinfunction "DET_G4") (pintype "passive"))
    )
    (net (code "77") (name "unconnected-(J4-POL-PadG3)") (class "Default")
      (node (ref "J4") (pin "G3") (pinfunction "POL_G3") (pintype "passive"))
    )
    (net (code "78") (name "unconnected-(S1-A-Pad1)") (class "Default")
      (node (ref "S1") (pin "1") (pinfunction "A_1") (pintype "passive"))
    )
    (net (code "79") (name "unconnected-(S1-B-Pad4)") (class "Default")
      (node (ref "S1") (pin "4") (pinfunction "B_4") (pintype "passive"))
    )
    (net (code "80") (name "unconnected-(S2-A-Pad1)") (class "Default")
      (node (ref "S2") (pin "1") (pinfunction "A_1") (pintype "passive"))
    )
    (net (code "81") (name "unconnected-(S2-B-Pad4)") (class "Default")
      (node (ref "S2") (pin "4") (pinfunction "B_4") (pintype "passive"))
    )
  )
)
